# IV6_general_schema.net
KiCad netlist of a schematic drawn in EAGLE
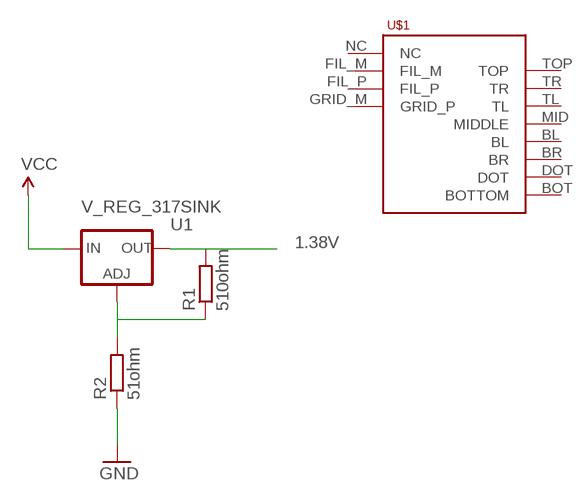
[diagram p0: schematic, sheet 1]

(export (version "E")
  (design (tool "Eeschema 10.0.6"))
  (components
    (comp (ref "R1")
      (value "510ohm")
      (footprint "eagle-import:0204_7")
      (libsource (lib "eagle-import") (part "R-EU_0204/7"))
    )
    (comp (ref "R2")
      (value "51ohm")
      (footprint "eagle-import:0204_7")
      (libsource (lib "eagle-import") (part "R-EU_0204/7"))
    )
    (comp (ref "U$1")
      (value "IV6_NUMITRON")
      (footprint "eagle-import:IV6_NUMITRON_PAC")
      (libsource (lib "eagle-import") (part "IV6_NUMITRON"))
    )
    (comp (ref "U1")
      (value "V_REG_317SINK")
      (footprint "eagle-import:TO220-ADJ")
      (libsource (lib "eagle-import") (part "V_REG_317SINK"))
    )
  )
  (nets
    (net (code "1") (name "GND") (class "Default")
      (node (ref "R2") (pin "1") (pinfunction "1_1") (pintype "passive"))
    )
    (net (code "2") (name "Net-(R1-Pad1)") (class "Default")
      (node (ref "R1") (pin "1") (pinfunction "1_1") (pintype "passive"))
      (node (ref "R2") (pin "2") (pinfunction "2_2") (pintype "passive"))
      (node (ref "U1") (pin "ADJ") (pinfunction "ADJ_ADJ") (pintype "input"))
    )
    (net (code "3") (name "Net-(R1-Pad2)") (class "Default")
      (node (ref "R1") (pin "2") (pinfunction "2_2") (pintype "passive"))
      (node (ref "U1") (pin "OUT") (pinfunction "OUT_OUT") (pintype "output"))
    )
    (net (code "4") (name "VCC") (class "Default")
      (node (ref "U1") (pin "IN") (pinfunction "IN_IN") (pintype "input"))
    )
    (net (code "5") (name "unconnected-(U$1-BOTTOM-PadBOT)") (class "Default")
      (node (ref "U$1") (pin "BOT") (pinfunction "BOTTOM_BOT") (pintype "bidirectional"))
    )
    (net (code "6") (name "unconnected-(U$1-GRID_P-PadGRID_M)") (class "Default")
      (node (ref "U$1") (pin "GRID_M") (pinfunction "GRID_P_GRID_M") (pintype "bidirectional"))
    )
    (net (code "7") (name "unconnected-(U$1-MIDDLE-PadMID)") (class "Default")
      (node (ref "U$1") (pin "MID") (pinfunction "MIDDLE_MID") (pintype "bidirectional"))
    )
    (net (code "8") (name "unconnected-(U$1-PadBL)") (class "Default")
      (node (ref "U$1") (pin "BL") (pinfunction "BL_BL") (pintype "bidirectional"))
    )
    (net (code "9") (name "unconnected-(U$1-PadBR)") (class "Default")
      (node (ref "U$1") (pin "BR") (pinfunction "BR_BR") (pintype "bidirectional"))
    )
    (net (code "10") (name "unconnected-(U$1-PadDOT)") (class "Default")
      (node (ref "U$1") (pin "DOT") (pinfunction "DOT_DOT") (pintype "bidirectional"))
    )
    (net (code "11") (name "unconnected-(U$1-PadFIL_M)") (class "Default")
      (node (ref "U$1") (pin "FIL_M") (pinfunction "FIL_M_FIL_M") (pintype "bidirectional"))
    )
    (net (code "12") (name "unconnected-(U$1-PadFIL_P)") (class "Default")
      (node (ref "U$1") (pin "FIL_P") (pinfunction "FIL_P_FIL_P") (pintype "bidirectional"))
    )
    (net (code "13") (name "unconnected-(U$1-PadNC)") (class "Default")
      (node (ref "U$1") (pin "NC") (pinfunction "NC_NC") (pintype "bidirectional"))
    )
    (net (code "14") (name "unconnected-(U$1-PadTL)") (class "Default")
      (node (ref "U$1") (pin "TL") (pinfunction "TL_TL") (pintype "bidirectional"))
    )
    (net (code "15") (name "unconnected-(U$1-PadTOP)") (class "Default")
      (node (ref "U$1") (pin "TOP") (pinfunction "TOP_TOP") (pintype "bidirectional"))
    )
    (net (code "16") (name "unconnected-(U$1-PadTR)") (class "Default")
      (node (ref "U$1") (pin "TR") (pinfunction "TR_TR") (pintype "bidirectional"))
    )
  )
)
